# 06-Front_Panel_SFP_2.net
KiCad netlist of a schematic drawn in Altium Designer
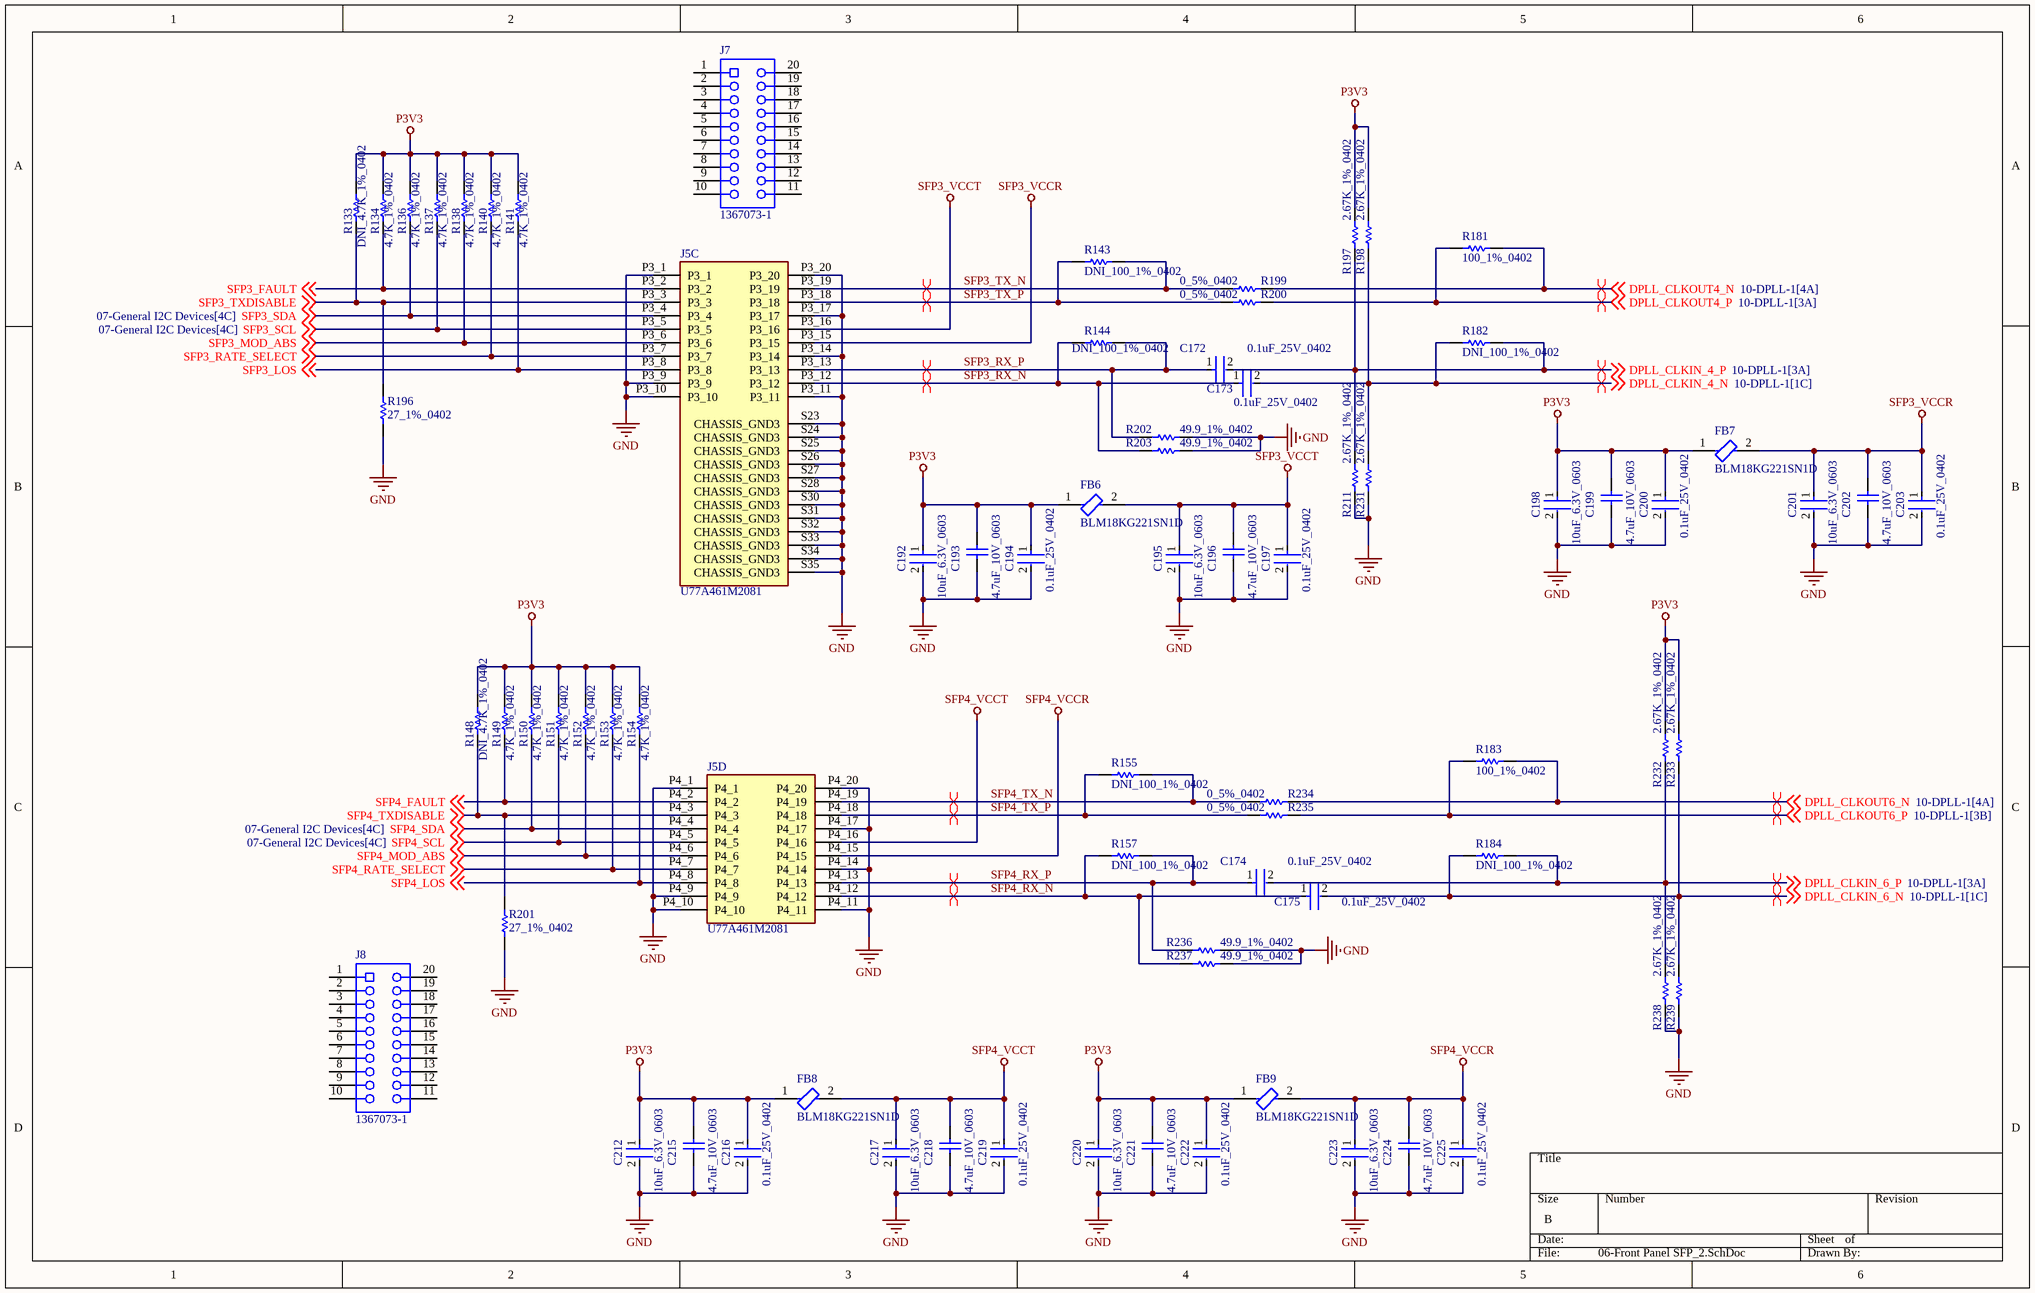
[diagram p0: 06-Front Panel SFP_2.SchDoc]

(export (version "E")
  (design (tool "Eeschema 10.0.6"))
  (components
    (comp (ref "C172")
      (value "0.1uF_25V_0402")
      (footprint "FP-0402-L_1_0_1-W_0_5_0_1-IPC_C")
      (description "General Purpose Ceramic Capacitor, 0402, 100nF, 10%, X7R, 15%, 25V")
      (fields (field (name "VOLTAGE") "25V") (field (name "TOLERANCE") "10%"))
      (libsource (lib "Altium Content Vault") (part "b4654b650e69147ec39a6b967a45e02"))
    )
    (comp (ref "C173")
      (value "0.1uF_25V_0402")
      (footprint "FP-0402-L_1_0_1-W_0_5_0_1-IPC_C")
      (description "General Purpose Ceramic Capacitor, 0402, 100nF, 10%, X7R, 15%, 25V")
      (fields (field (name "VOLTAGE") "25V") (field (name "TOLERANCE") "10%"))
      (libsource (lib "Altium Content Vault") (part "b4654b650e69147ec39a6b967a45e02"))
    )
    (comp (ref "C174")
      (value "0.1uF_25V_0402")
      (footprint "FP-0402-L_1_0_1-W_0_5_0_1-IPC_C")
      (description "General Purpose Ceramic Capacitor, 0402, 100nF, 10%, X7R, 15%, 25V")
      (fields (field (name "VOLTAGE") "25V") (field (name "TOLERANCE") "10%"))
      (libsource (lib "Altium Content Vault") (part "b4654b650e69147ec39a6b967a45e02"))
    )
    (comp (ref "C175")
      (value "0.1uF_25V_0402")
      (footprint "FP-0402-L_1_0_1-W_0_5_0_1-IPC_C")
      (description "General Purpose Ceramic Capacitor, 0402, 100nF, 10%, X7R, 15%, 25V")
      (fields (field (name "VOLTAGE") "25V") (field (name "TOLERANCE") "10%"))
      (libsource (lib "Altium Content Vault") (part "b4654b650e69147ec39a6b967a45e02"))
    )
    (comp (ref "C192")
      (value "10uF_6.3V_0603")
      (footprint "FP-C0603C106M9PACTU-MFG")
      (description "CAP CER 10UF 6.3V X5R 0603")
      (fields
        (field (name "MANUFACTURER PART NUMBER") "C0603C106M9PACTU")
        (field (name "MANUFACTURER") "Kemet")
      )
      (libsource (lib "Altium Content Vault") (part "b4654b650e69147ec39a6b967a45e02"))
    )
    (comp (ref "C193")
      (value "4.7uF_10V_0603")
      (footprint "CAPC1608X87X35NL15T15")
      (fields (field (name "PART NUMBER") "C0603C475K8PACTU") (field (name "MANUFACTURER") "Kemet"))
      (libsource (lib "Altium Content Vault") (part "CAP"))
    )
    (comp (ref "C194")
      (value "0.1uF_25V_0402")
      (footprint "FP-0402-L_1_0_1-W_0_5_0_1-IPC_C")
      (description "General Purpose Ceramic Capacitor, 0402, 100nF, 10%, X7R, 15%, 25V")
      (fields (field (name "VOLTAGE") "25V") (field (name "TOLERANCE") "10%"))
      (libsource (lib "Altium Content Vault") (part "b4654b650e69147ec39a6b967a45e02"))
    )
    (comp (ref "C195")
      (value "10uF_6.3V_0603")
      (footprint "FP-C0603C106M9PACTU-MFG")
      (description "CAP CER 10UF 6.3V X5R 0603")
      (fields
        (field (name "MANUFACTURER PART NUMBER") "C0603C106M9PACTU")
        (field (name "MANUFACTURER") "Kemet")
      )
      (libsource (lib "Altium Content Vault") (part "b4654b650e69147ec39a6b967a45e02"))
    )
    (comp (ref "C196")
      (value "4.7uF_10V_0603")
      (footprint "CAPC1608X87X35NL15T15")
      (fields (field (name "PART NUMBER") "C0603C475K8PACTU") (field (name "MANUFACTURER") "Kemet"))
      (libsource (lib "Altium Content Vault") (part "CAP"))
    )
    (comp (ref "C197")
      (value "0.1uF_25V_0402")
      (footprint "FP-0402-L_1_0_1-W_0_5_0_1-IPC_C")
      (description "General Purpose Ceramic Capacitor, 0402, 100nF, 10%, X7R, 15%, 25V")
      (fields (field (name "VOLTAGE") "25V") (field (name "TOLERANCE") "10%"))
      (libsource (lib "Altium Content Vault") (part "b4654b650e69147ec39a6b967a45e02"))
    )
    (comp (ref "C198")
      (value "10uF_6.3V_0603")
      (footprint "FP-C0603C106M9PACTU-MFG")
      (description "CAP CER 10UF 6.3V X5R 0603")
      (fields
        (field (name "MANUFACTURER PART NUMBER") "C0603C106M9PACTU")
        (field (name "MANUFACTURER") "Kemet")
      )
      (libsource (lib "Altium Content Vault") (part "b4654b650e69147ec39a6b967a45e02"))
    )
    (comp (ref "C199")
      (value "4.7uF_10V_0603")
      (footprint "CAPC1608X87X35NL15T15")
      (fields (field (name "PART NUMBER") "C0603C475K8PACTU") (field (name "MANUFACTURER") "Kemet"))
      (libsource (lib "Altium Content Vault") (part "CAP"))
    )
    (comp (ref "C200")
      (value "0.1uF_25V_0402")
      (footprint "FP-0402-L_1_0_1-W_0_5_0_1-IPC_C")
      (description "General Purpose Ceramic Capacitor, 0402, 100nF, 10%, X7R, 15%, 25V")
      (fields (field (name "VOLTAGE") "25V") (field (name "TOLERANCE") "10%"))
      (libsource (lib "Altium Content Vault") (part "b4654b650e69147ec39a6b967a45e02"))
    )
    (comp (ref "C201")
      (value "10uF_6.3V_0603")
      (footprint "FP-C0603C106M9PACTU-MFG")
      (description "CAP CER 10UF 6.3V X5R 0603")
      (fields
        (field (name "MANUFACTURER PART NUMBER") "C0603C106M9PACTU")
        (field (name "MANUFACTURER") "Kemet")
      )
      (libsource (lib "Altium Content Vault") (part "b4654b650e69147ec39a6b967a45e02"))
    )
    (comp (ref "C202")
      (value "4.7uF_10V_0603")
      (footprint "CAPC1608X87X35NL15T15")
      (fields (field (name "PART NUMBER") "C0603C475K8PACTU") (field (name "MANUFACTURER") "Kemet"))
      (libsource (lib "Altium Content Vault") (part "CAP"))
    )
    (comp (ref "C203")
      (value "0.1uF_25V_0402")
      (footprint "FP-0402-L_1_0_1-W_0_5_0_1-IPC_C")
      (description "General Purpose Ceramic Capacitor, 0402, 100nF, 10%, X7R, 15%, 25V")
      (fields (field (name "VOLTAGE") "25V") (field (name "TOLERANCE") "10%"))
      (libsource (lib "Altium Content Vault") (part "b4654b650e69147ec39a6b967a45e02"))
    )
    (comp (ref "C212")
      (value "10uF_6.3V_0603")
      (footprint "FP-C0603C106M9PACTU-MFG")
      (description "CAP CER 10UF 6.3V X5R 0603")
      (fields
        (field (name "MANUFACTURER PART NUMBER") "C0603C106M9PACTU")
        (field (name "MANUFACTURER") "Kemet")
      )
      (libsource (lib "Altium Content Vault") (part "b4654b650e69147ec39a6b967a45e02"))
    )
    (comp (ref "C215")
      (value "4.7uF_10V_0603")
      (footprint "CAPC1608X87X35NL15T15")
      (fields (field (name "PART NUMBER") "C0603C475K8PACTU") (field (name "MANUFACTURER") "Kemet"))
      (libsource (lib "Altium Content Vault") (part "CAP"))
    )
    (comp (ref "C216")
      (value "0.1uF_25V_0402")
      (footprint "FP-0402-L_1_0_1-W_0_5_0_1-IPC_C")
      (description "General Purpose Ceramic Capacitor, 0402, 100nF, 10%, X7R, 15%, 25V")
      (fields (field (name "VOLTAGE") "25V") (field (name "TOLERANCE") "10%"))
      (libsource (lib "Altium Content Vault") (part "b4654b650e69147ec39a6b967a45e02"))
    )
    (comp (ref "C217")
      (value "10uF_6.3V_0603")
      (footprint "FP-C0603C106M9PACTU-MFG")
      (description "CAP CER 10UF 6.3V X5R 0603")
      (fields
        (field (name "MANUFACTURER PART NUMBER") "C0603C106M9PACTU")
        (field (name "MANUFACTURER") "Kemet")
      )
      (libsource (lib "Altium Content Vault") (part "b4654b650e69147ec39a6b967a45e02"))
    )
    (comp (ref "C218")
      (value "4.7uF_10V_0603")
      (footprint "CAPC1608X87X35NL15T15")
      (fields (field (name "PART NUMBER") "C0603C475K8PACTU") (field (name "MANUFACTURER") "Kemet"))
      (libsource (lib "Altium Content Vault") (part "CAP"))
    )
    (comp (ref "C219")
      (value "0.1uF_25V_0402")
      (footprint "FP-0402-L_1_0_1-W_0_5_0_1-IPC_C")
      (description "General Purpose Ceramic Capacitor, 0402, 100nF, 10%, X7R, 15%, 25V")
      (fields (field (name "VOLTAGE") "25V") (field (name "TOLERANCE") "10%"))
      (libsource (lib "Altium Content Vault") (part "b4654b650e69147ec39a6b967a45e02"))
    )
    (comp (ref "C220")
      (value "10uF_6.3V_0603")
      (footprint "FP-C0603C106M9PACTU-MFG")
      (description "CAP CER 10UF 6.3V X5R 0603")
      (fields
        (field (name "MANUFACTURER PART NUMBER") "C0603C106M9PACTU")
        (field (name "MANUFACTURER") "Kemet")
      )
      (libsource (lib "Altium Content Vault") (part "b4654b650e69147ec39a6b967a45e02"))
    )
    (comp (ref "C221")
      (value "4.7uF_10V_0603")
      (footprint "CAPC1608X87X35NL15T15")
      (fields (field (name "PART NUMBER") "C0603C475K8PACTU") (field (name "MANUFACTURER") "Kemet"))
      (libsource (lib "Altium Content Vault") (part "CAP"))
    )
    (comp (ref "C222")
      (value "0.1uF_25V_0402")
      (footprint "FP-0402-L_1_0_1-W_0_5_0_1-IPC_C")
      (description "General Purpose Ceramic Capacitor, 0402, 100nF, 10%, X7R, 15%, 25V")
      (fields (field (name "VOLTAGE") "25V") (field (name "TOLERANCE") "10%"))
      (libsource (lib "Altium Content Vault") (part "b4654b650e69147ec39a6b967a45e02"))
    )
    (comp (ref "C223")
      (value "10uF_6.3V_0603")
      (footprint "FP-C0603C106M9PACTU-MFG")
      (description "CAP CER 10UF 6.3V X5R 0603")
      (fields
        (field (name "MANUFACTURER PART NUMBER") "C0603C106M9PACTU")
        (field (name "MANUFACTURER") "Kemet")
      )
      (libsource (lib "Altium Content Vault") (part "b4654b650e69147ec39a6b967a45e02"))
    )
    (comp (ref "C224")
      (value "4.7uF_10V_0603")
      (footprint "CAPC1608X87X35NL15T15")
      (fields (field (name "PART NUMBER") "C0603C475K8PACTU") (field (name "MANUFACTURER") "Kemet"))
      (libsource (lib "Altium Content Vault") (part "CAP"))
    )
    (comp (ref "C225")
      (value "0.1uF_25V_0402")
      (footprint "FP-0402-L_1_0_1-W_0_5_0_1-IPC_C")
      (description "General Purpose Ceramic Capacitor, 0402, 100nF, 10%, X7R, 15%, 25V")
      (fields (field (name "VOLTAGE") "25V") (field (name "TOLERANCE") "10%"))
      (libsource (lib "Altium Content Vault") (part "b4654b650e69147ec39a6b967a45e02"))
    )
    (comp (ref "FB6")
      (value "BLM18KG221SN1D")
      (footprint "FP-BLM18-0_15-t0_8-IPC_B")
      (description "Chip Ferrite Bead, 0603, 220Ω @ 100MHz, 0.05Ω, 25%, 2.2A")
      (fields (field (name "TOLERANCE") "25%"))
      (libsource (lib "Altium Content Vault") (part "5f30dd21d616792df468990f7003faa"))
    )
    (comp (ref "FB7")
      (value "BLM18KG221SN1D")
      (footprint "FP-BLM18-0_15-t0_8-IPC_B")
      (description "Chip Ferrite Bead, 0603, 220Ω @ 100MHz, 0.05Ω, 25%, 2.2A")
      (fields (field (name "TOLERANCE") "25%"))
      (libsource (lib "Altium Content Vault") (part "5f30dd21d616792df468990f7003faa"))
    )
    (comp (ref "FB8")
      (value "BLM18KG221SN1D")
      (footprint "FP-BLM18-0_15-t0_8-IPC_B")
      (description "Chip Ferrite Bead, 0603, 220Ω @ 100MHz, 0.05Ω, 25%, 2.2A")
      (fields (field (name "TOLERANCE") "25%"))
      (libsource (lib "Altium Content Vault") (part "5f30dd21d616792df468990f7003faa"))
    )
    (comp (ref "FB9")
      (value "BLM18KG221SN1D")
      (footprint "FP-BLM18-0_15-t0_8-IPC_B")
      (description "Chip Ferrite Bead, 0603, 220Ω @ 100MHz, 0.05Ω, 25%, 2.2A")
      (fields (field (name "TOLERANCE") "25%"))
      (libsource (lib "Altium Content Vault") (part "5f30dd21d616792df468990f7003faa"))
    )
    (comp (ref "J5")
      (value "U77A461M2081")
      (footprint "AMPHENOL_U77A461M2081")
      (fields (field (name "MF") "AMPHENOL ICC / FCI"))
      (libsource (lib "U77A461M2081") (part "U77A461M2081"))
    )
    (comp (ref "J7")
      (value "1367073-1")
      (footprint "TECO-1367073-1_V")
      (fields (field (name "MANUFACTURER") "TE Connectivity"))
      (libsource (lib "Altium Content Vault") (part "CN-2P-F-R20_B"))
    )
    (comp (ref "J8")
      (value "1367073-1")
      (footprint "TECO-1367073-1_V")
      (fields (field (name "MANUFACTURER") "TE Connectivity"))
      (libsource (lib "Altium Content Vault") (part "CN-2P-F-R20_B"))
    )
    (comp (ref "R133")
      (value "DNI_4.7K_1%_0402")
      (footprint "RESC1005X40X25NL10T10")
      (fields (field (name "MANUFACTURER") "Bourns") (field (name "PART NUMBER") "CR0402-FX-4701GLF"))
      (libsource (lib "Altium Content Vault") (part "RES"))
    )
    (comp (ref "R134")
      (value "4.7K_1%_0402")
      (footprint "RESC1005X40X25NL10T10")
      (fields (field (name "MANUFACTURER") "Bourns") (field (name "PART NUMBER") "CR0402-FX-4701GLF"))
      (libsource (lib "Altium Content Vault") (part "RES"))
    )
    (comp (ref "R136")
      (value "4.7K_1%_0402")
      (footprint "RESC1005X40X25NL10T10")
      (fields (field (name "MANUFACTURER") "Bourns") (field (name "PART NUMBER") "CR0402-FX-4701GLF"))
      (libsource (lib "Altium Content Vault") (part "RES"))
    )
    (comp (ref "R137")
      (value "4.7K_1%_0402")
      (footprint "RESC1005X40X25NL10T10")
      (fields (field (name "MANUFACTURER") "Bourns") (field (name "PART NUMBER") "CR0402-FX-4701GLF"))
      (libsource (lib "Altium Content Vault") (part "RES"))
    )
    (comp (ref "R138")
      (value "4.7K_1%_0402")
      (footprint "RESC1005X40X25NL10T10")
      (fields (field (name "MANUFACTURER") "Bourns") (field (name "PART NUMBER") "CR0402-FX-4701GLF"))
      (libsource (lib "Altium Content Vault") (part "RES"))
    )
    (comp (ref "R140")
      (value "4.7K_1%_0402")
      (footprint "RESC1005X40X25NL10T10")
      (fields (field (name "MANUFACTURER") "Bourns") (field (name "PART NUMBER") "CR0402-FX-4701GLF"))
      (libsource (lib "Altium Content Vault") (part "RES"))
    )
    (comp (ref "R141")
      (value "4.7K_1%_0402")
      (footprint "RESC1005X40X25NL10T10")
      (fields (field (name "MANUFACTURER") "Bourns") (field (name "PART NUMBER") "CR0402-FX-4701GLF"))
      (libsource (lib "Altium Content Vault") (part "RES"))
    )
    (comp (ref "R143")
      (value "DNI_100_1%_0402")
      (footprint "RESC1005X40X25NL05T10")
      (fields (field (name "MANUFACTURER") "Yageo") (field (name "PART NUMBER") "RC0402FR-13100RL"))
      (libsource (lib "Altium Content Vault") (part "RES"))
    )
    (comp (ref "R144")
      (value "DNI_100_1%_0402")
      (footprint "RESC1005X40X25NL05T10")
      (fields (field (name "MANUFACTURER") "Yageo") (field (name "PART NUMBER") "RC0402FR-13100RL"))
      (libsource (lib "Altium Content Vault") (part "RES"))
    )
    (comp (ref "R148")
      (value "DNI_4.7K_1%_0402")
      (footprint "RESC1005X40X25NL10T10")
      (fields (field (name "MANUFACTURER") "Bourns") (field (name "PART NUMBER") "CR0402-FX-4701GLF"))
      (libsource (lib "Altium Content Vault") (part "RES"))
    )
    (comp (ref "R149")
      (value "4.7K_1%_0402")
      (footprint "RESC1005X40X25NL10T10")
      (fields (field (name "MANUFACTURER") "Bourns") (field (name "PART NUMBER") "CR0402-FX-4701GLF"))
      (libsource (lib "Altium Content Vault") (part "RES"))
    )
    (comp (ref "R150")
      (value "4.7K_1%_0402")
      (footprint "RESC1005X40X25NL10T10")
      (fields (field (name "MANUFACTURER") "Bourns") (field (name "PART NUMBER") "CR0402-FX-4701GLF"))
      (libsource (lib "Altium Content Vault") (part "RES"))
    )
    (comp (ref "R151")
      (value "4.7K_1%_0402")
      (footprint "RESC1005X40X25NL10T10")
      (fields (field (name "MANUFACTURER") "Bourns") (field (name "PART NUMBER") "CR0402-FX-4701GLF"))
      (libsource (lib "Altium Content Vault") (part "RES"))
    )
    (comp (ref "R152")
      (value "4.7K_1%_0402")
      (footprint "RESC1005X40X25NL10T10")
      (fields (field (name "MANUFACTURER") "Bourns") (field (name "PART NUMBER") "CR0402-FX-4701GLF"))
      (libsource (lib "Altium Content Vault") (part "RES"))
    )
    (comp (ref "R153")
      (value "4.7K_1%_0402")
      (footprint "RESC1005X40X25NL10T10")
      (fields (field (name "MANUFACTURER") "Bourns") (field (name "PART NUMBER") "CR0402-FX-4701GLF"))
      (libsource (lib "Altium Content Vault") (part "RES"))
    )
    (comp (ref "R154")
      (value "4.7K_1%_0402")
      (footprint "RESC1005X40X25NL10T10")
      (fields (field (name "MANUFACTURER") "Bourns") (field (name "PART NUMBER") "CR0402-FX-4701GLF"))
      (libsource (lib "Altium Content Vault") (part "RES"))
    )
    (comp (ref "R155")
      (value "DNI_100_1%_0402")
      (footprint "RESC1005X40X25NL05T10")
      (fields (field (name "MANUFACTURER") "Yageo") (field (name "PART NUMBER") "RC0402FR-13100RL"))
      (libsource (lib "Altium Content Vault") (part "RES"))
    )
    (comp (ref "R157")
      (value "DNI_100_1%_0402")
      (footprint "RESC1005X40X25NL05T10")
      (fields (field (name "MANUFACTURER") "Yageo") (field (name "PART NUMBER") "RC0402FR-13100RL"))
      (libsource (lib "Altium Content Vault") (part "RES"))
    )
    (comp (ref "R181")
      (value "100_1%_0402")
      (footprint "RESC1005X40X25NL05T10")
      (fields (field (name "MANUFACTURER") "Yageo") (field (name "PART NUMBER") "RC0402FR-13100RL"))
      (libsource (lib "Altium Content Vault") (part "RES"))
    )
    (comp (ref "R182")
      (value "DNI_100_1%_0402")
      (footprint "RESC1005X40X25NL05T10")
      (fields (field (name "MANUFACTURER") "Yageo") (field (name "PART NUMBER") "RC0402FR-13100RL"))
      (libsource (lib "Altium Content Vault") (part "RES"))
    )
    (comp (ref "R183")
      (value "100_1%_0402")
      (footprint "RESC1005X40X25NL05T10")
      (fields (field (name "MANUFACTURER") "Yageo") (field (name "PART NUMBER") "RC0402FR-13100RL"))
      (libsource (lib "Altium Content Vault") (part "RES"))
    )
    (comp (ref "R184")
      (value "DNI_100_1%_0402")
      (footprint "RESC1005X40X25NL05T10")
      (fields (field (name "MANUFACTURER") "Yageo") (field (name "PART NUMBER") "RC0402FR-13100RL"))
      (libsource (lib "Altium Content Vault") (part "RES"))
    )
    (comp (ref "R196")
      (value "27_1%_0402")
      (footprint "RESC1005X40X25NL05T05")
      (fields (field (name "PART NUMBER") "CRCW040227R0FKED") (field (name "MANUFACTURER") "Vishay Dale"))
      (libsource (lib "Altium Content Vault") (part "RES"))
    )
    (comp (ref "R197")
      (value "2.67K_1%_0402")
      (footprint "RESC1005X40X25NL05T10")
      (fields (field (name "MANUFACTURER") "Yageo") (field (name "PART NUMBER") "RC0402FR-072K67L"))
      (libsource (lib "Altium Content Vault") (part "RES"))
    )
    (comp (ref "R198")
      (value "2.67K_1%_0402")
      (footprint "RESC1005X40X25NL05T10")
      (fields (field (name "MANUFACTURER") "Yageo") (field (name "PART NUMBER") "RC0402FR-072K67L"))
      (libsource (lib "Altium Content Vault") (part "RES"))
    )
    (comp (ref "R199")
      (value "0_5%_0402")
      (footprint "RESC1005X40X25LL10T10")
      (fields (field (name "MANUFACTURER") "KOA Speer") (field (name "PART NUMBER") "RK73Z1ETTP"))
      (libsource (lib "Altium Content Vault") (part "RES"))
    )
    (comp (ref "R200")
      (value "0_5%_0402")
      (footprint "RESC1005X40X25LL10T10")
      (fields (field (name "MANUFACTURER") "KOA Speer") (field (name "PART NUMBER") "RK73Z1ETTP"))
      (libsource (lib "Altium Content Vault") (part "RES"))
    )
    (comp (ref "R201")
      (value "27_1%_0402")
      (footprint "RESC1005X40X25NL05T05")
      (fields (field (name "PART NUMBER") "CRCW040227R0FKED") (field (name "MANUFACTURER") "Vishay Dale"))
      (libsource (lib "Altium Content Vault") (part "RES"))
    )
    (comp (ref "R202")
      (value "49.9_1%_0402")
      (footprint "RESC1005X40X25NL10T10")
      (fields (field (name "PART NUMBER") "RK73H1ETTP49R9F") (field (name "MANUFACTURER") "KOA Speer"))
      (libsource (lib "Altium Content Vault") (part "RES"))
    )
    (comp (ref "R203")
      (value "49.9_1%_0402")
      (footprint "RESC1005X40X25NL10T10")
      (fields (field (name "PART NUMBER") "RK73H1ETTP49R9F") (field (name "MANUFACTURER") "KOA Speer"))
      (libsource (lib "Altium Content Vault") (part "RES"))
    )
    (comp (ref "R211")
      (value "2.67K_1%_0402")
      (footprint "RESC1005X40X25NL05T10")
      (fields (field (name "MANUFACTURER") "Yageo") (field (name "PART NUMBER") "RC0402FR-072K67L"))
      (libsource (lib "Altium Content Vault") (part "RES"))
    )
    (comp (ref "R231")
      (value "2.67K_1%_0402")
      (footprint "RESC1005X40X25NL05T10")
      (fields (field (name "MANUFACTURER") "Yageo") (field (name "PART NUMBER") "RC0402FR-072K67L"))
      (libsource (lib "Altium Content Vault") (part "RES"))
    )
    (comp (ref "R232")
      (value "2.67K_1%_0402")
      (footprint "RESC1005X40X25NL05T10")
      (fields (field (name "MANUFACTURER") "Yageo") (field (name "PART NUMBER") "RC0402FR-072K67L"))
      (libsource (lib "Altium Content Vault") (part "RES"))
    )
    (comp (ref "R233")
      (value "2.67K_1%_0402")
      (footprint "RESC1005X40X25NL05T10")
      (fields (field (name "MANUFACTURER") "Yageo") (field (name "PART NUMBER") "RC0402FR-072K67L"))
      (libsource (lib "Altium Content Vault") (part "RES"))
    )
    (comp (ref "R234")
      (value "0_5%_0402")
      (footprint "RESC1005X40X25LL10T10")
      (fields (field (name "MANUFACTURER") "KOA Speer") (field (name "PART NUMBER") "RK73Z1ETTP"))
      (libsource (lib "Altium Content Vault") (part "RES"))
    )
    (comp (ref "R235")
      (value "0_5%_0402")
      (footprint "RESC1005X40X25LL10T10")
      (fields (field (name "MANUFACTURER") "KOA Speer") (field (name "PART NUMBER") "RK73Z1ETTP"))
      (libsource (lib "Altium Content Vault") (part "RES"))
    )
    (comp (ref "R236")
      (value "49.9_1%_0402")
      (footprint "RESC1005X40X25NL10T10")
      (fields (field (name "PART NUMBER") "RK73H1ETTP49R9F") (field (name "MANUFACTURER") "KOA Speer"))
      (libsource (lib "Altium Content Vault") (part "RES"))
    )
    (comp (ref "R237")
      (value "49.9_1%_0402")
      (footprint "RESC1005X40X25NL10T10")
      (fields (field (name "PART NUMBER") "RK73H1ETTP49R9F") (field (name "MANUFACTURER") "KOA Speer"))
      (libsource (lib "Altium Content Vault") (part "RES"))
    )
    (comp (ref "R238")
      (value "2.67K_1%_0402")
      (footprint "RESC1005X40X25NL05T10")
      (fields (field (name "MANUFACTURER") "Yageo") (field (name "PART NUMBER") "RC0402FR-072K67L"))
      (libsource (lib "Altium Content Vault") (part "RES"))
    )
    (comp (ref "R239")
      (value "2.67K_1%_0402")
      (footprint "RESC1005X40X25NL05T10")
      (fields (field (name "MANUFACTURER") "Yageo") (field (name "PART NUMBER") "RC0402FR-072K67L"))
      (libsource (lib "Altium Content Vault") (part "RES"))
    )
  )
  (nets
    (net (code "1") (name "/SFP3_RX_N") (class "Default")
      (node (ref "C173") (pin "1") (pinfunction "1_1") (pintype "passive"))
      (node (ref "J5") (pin "P3_12") (pinfunction "P3_12_P3_12") (pintype "passive"))
      (node (ref "R144") (pin "1") (pinfunction "1_1") (pintype "passive"))
      (node (ref "R203") (pin "1") (pinfunction "1_1") (pintype "passive"))
    )
    (net (code "2") (name "/SFP3_RX_P") (class "Default")
      (node (ref "C172") (pin "1") (pinfunction "1_1") (pintype "passive"))
      (node (ref "J5") (pin "P3_13") (pinfunction "P3_13_P3_13") (pintype "passive"))
      (node (ref "R144") (pin "2") (pinfunction "2_2") (pintype "passive"))
      (node (ref "R202") (pin "1") (pinfunction "1_1") (pintype "passive"))
    )
    (net (code "3") (name "/SFP3_TX_N") (class "Default")
      (node (ref "J5") (pin "P3_19") (pinfunction "P3_19_P3_19") (pintype "passive"))
      (node (ref "R143") (pin "2") (pinfunction "2_2") (pintype "passive"))
      (node (ref "R199") (pin "1") (pinfunction "1_1") (pintype "passive"))
    )
    (net (code "4") (name "/SFP3_TX_P") (class "Default")
      (node (ref "J5") (pin "P3_18") (pinfunction "P3_18_P3_18") (pintype "passive"))
      (node (ref "R143") (pin "1") (pinfunction "1_1") (pintype "passive"))
      (node (ref "R200") (pin "1") (pinfunction "1_1") (pintype "passive"))
    )
    (net (code "5") (name "/SFP4_RX_N") (class "Default")
      (node (ref "C175") (pin "1") (pinfunction "1_1") (pintype "passive"))
      (node (ref "J5") (pin "P4_12") (pinfunction "P4_12_P4_12") (pintype "passive"))
      (node (ref "R157") (pin "1") (pinfunction "1_1") (pintype "passive"))
      (node (ref "R237") (pin "1") (pinfunction "1_1") (pintype "passive"))
    )
    (net (code "6") (name "/SFP4_RX_P") (class "Default")
      (node (ref "C174") (pin "1") (pinfunction "1_1") (pintype "passive"))
      (node (ref "J5") (pin "P4_13") (pinfunction "P4_13_P4_13") (pintype "passive"))
      (node (ref "R157") (pin "2") (pinfunction "2_2") (pintype "passive"))
      (node (ref "R236") (pin "1") (pinfunction "1_1") (pintype "passive"))
    )
    (net (code "7") (name "/SFP4_TX_N") (class "Default")
      (node (ref "J5") (pin "P4_19") (pinfunction "P4_19_P4_19") (pintype "passive"))
      (node (ref "R155") (pin "2") (pinfunction "2_2") (pintype "passive"))
      (node (ref "R234") (pin "1") (pinfunction "1_1") (pintype "passive"))
    )
    (net (code "8") (name "/SFP4_TX_P") (class "Default")
      (node (ref "J5") (pin "P4_18") (pinfunction "P4_18_P4_18") (pintype "passive"))
      (node (ref "R155") (pin "1") (pinfunction "1_1") (pintype "passive"))
      (node (ref "R235") (pin "1") (pinfunction "1_1") (pintype "passive"))
    )
    (net (code "9") (name "DPLL_CLKIN_4_N") (class "Default")
      (node (ref "C173") (pin "2") (pinfunction "2_2") (pintype "passive"))
      (node (ref "R182") (pin "1") (pinfunction "1_1") (pintype "passive"))
      (node (ref "R198") (pin "1") (pinfunction "1_1") (pintype "passive"))
      (node (ref "R231") (pin "2") (pinfunction "2_2") (pintype "passive"))
    )
    (net (code "10") (name "DPLL_CLKIN_4_P") (class "Default")
      (node (ref "C172") (pin "2") (pinfunction "2_2") (pintype "passive"))
      (node (ref "R182") (pin "2") (pinfunction "2_2") (pintype "passive"))
      (node (ref "R197") (pin "1") (pinfunction "1_1") (pintype "passive"))
      (node (ref "R211") (pin "2") (pinfunction "2_2") (pintype "passive"))
    )
    (net (code "11") (name "DPLL_CLKIN_6_N") (class "Default")
      (node (ref "C175") (pin "2") (pinfunction "2_2") (pintype "passive"))
      (node (ref "R184") (pin "1") (pinfunction "1_1") (pintype "passive"))
      (node (ref "R233") (pin "1") (pinfunction "1_1") (pintype "passive"))
      (node (ref "R239") (pin "2") (pinfunction "2_2") (pintype "passive"))
    )
    (net (code "12") (name "DPLL_CLKIN_6_P") (class "Default")
      (node (ref "C174") (pin "2") (pinfunction "2_2") (pintype "passive"))
      (node (ref "R184") (pin "2") (pinfunction "2_2") (pintype "passive"))
      (node (ref "R232") (pin "1") (pinfunction "1_1") (pintype "passive"))
      (node (ref "R238") (pin "2") (pinfunction "2_2") (pintype "passive"))
    )
    (net (code "13") (name "DPLL_CLKOUT4_N") (class "Default")
      (node (ref "R181") (pin "2") (pinfunction "2_2") (pintype "passive"))
      (node (ref "R199") (pin "2") (pinfunction "2_2") (pintype "passive"))
    )
    (net (code "14") (name "DPLL_CLKOUT4_P") (class "Default")
      (node (ref "R181") (pin "1") (pinfunction "1_1") (pintype "passive"))
      (node (ref "R200") (pin "2") (pinfunction "2_2") (pintype "passive"))
    )
    (net (code "15") (name "DPLL_CLKOUT6_N") (class "Default")
      (node (ref "R183") (pin "2") (pinfunction "2_2") (pintype "passive"))
      (node (ref "R234") (pin "2") (pinfunction "2_2") (pintype "passive"))
    )
    (net (code "16") (name "DPLL_CLKOUT6_P") (class "Default")
      (node (ref "R183") (pin "1") (pinfunction "1_1") (pintype "passive"))
      (node (ref "R235") (pin "2") (pinfunction "2_2") (pintype "passive"))
    )
    (net (code "17") (name "GND") (class "Default")
      (node (ref "C192") (pin "2") (pinfunction "2_2") (pintype "passive"))
      (node (ref "C193") (pin "1") (pinfunction "1_1") (pintype "passive"))
      (node (ref "C194") (pin "2") (pinfunction "2_2") (pintype "passive"))
      (node (ref "C195") (pin "2") (pinfunction "2_2") (pintype "passive"))
      (node (ref "C196") (pin "1") (pinfunction "1_1") (pintype "passive"))
      (node (ref "C197") (pin "2") (pinfunction "2_2") (pintype "passive"))
      (node (ref "C198") (pin "2") (pinfunction "2_2") (pintype "passive"))
      (node (ref "C199") (pin "1") (pinfunction "1_1") (pintype "passive"))
      (node (ref "C200") (pin "2") (pinfunction "2_2") (pintype "passive"))
      (node (ref "C201") (pin "2") (pinfunction "2_2") (pintype "passive"))
      (node (ref "C202") (pin "1") (pinfunction "1_1") (pintype "passive"))
      (node (ref "C203") (pin "2") (pinfunction "2_2") (pintype "passive"))
      (node (ref "C212") (pin "2") (pinfunction "2_2") (pintype "passive"))
      (node (ref "C215") (pin "1") (pinfunction "1_1") (pintype "passive"))
      (node (ref "C216") (pin "2") (pinfunction "2_2") (pintype "passive"))
      (node (ref "C217") (pin "2") (pinfunction "2_2") (pintype "passive"))
      (node (ref "C218") (pin "1") (pinfunction "1_1") (pintype "passive"))
      (node (ref "C219") (pin "2") (pinfunction "2_2") (pintype "passive"))
      (node (ref "C220") (pin "2") (pinfunction "2_2") (pintype "passive"))
      (node (ref "C221") (pin "1") (pinfunction "1_1") (pintype "passive"))
      (node (ref "C222") (pin "2") (pinfunction "2_2") (pintype "passive"))
      (node (ref "C223") (pin "2") (pinfunction "2_2") (pintype "passive"))
      (node (ref "C224") (pin "1") (pinfunction "1_1") (pintype "passive"))
      (node (ref "C225") (pin "2") (pinfunction "2_2") (pintype "passive"))
      (node (ref "J5") (pin "P3_1") (pinfunction "P3_1_P3_1") (pintype "passive"))
      (node (ref "J5") (pin "P3_10") (pinfunction "P3_10_P3_10") (pintype "passive"))
      (node (ref "J5") (pin "P3_11") (pinfunction "P3_11_P3_11") (pintype "passive"))
      (node (ref "J5") (pin "P3_14") (pinfunction "P3_14_P3_14") (pintype "passive"))
      (node (ref "J5") (pin "P3_17") (pinfunction "P3_17_P3_17") (pintype "passive"))
      (node (ref "J5") (pin "P3_20") (pinfunction "P3_20_P3_20") (pintype "passive"))
      (node (ref "J5") (pin "P3_9") (pinfunction "P3_9_P3_9") (pintype "passive"))
      (node (ref "J5") (pin "P4_1") (pinfunction "P4_1_P4_1") (pintype "passive"))
      (node (ref "J5") (pin "P4_10") (pinfunction "P4_10_P4_10") (pintype "passive"))
      (node (ref "J5") (pin "P4_11") (pinfunction "P4_11_P4_11") (pintype "passive"))
      (node (ref "J5") (pin "P4_14") (pinfunction "P4_14_P4_14") (pintype "passive"))
      (node (ref "J5") (pin "P4_17") (pinfunction "P4_17_P4_17") (pintype "passive"))
      (node (ref "J5") (pin "P4_20") (pinfunction "P4_20_P4_20") (pintype "passive"))
      (node (ref "J5") (pin "P4_9") (pinfunction "P4_9_P4_9") (pintype "passive"))
      (node (ref "J5") (pin "S23") (pinfunction "CHASSIS_GND3_S23") (pintype "passive"))
      (node (ref "J5") (pin "S24") (pinfunction "CHASSIS_GND3_S24") (pintype "passive"))
      (node (ref "J5") (pin "S25") (pinfunction "CHASSIS_GND3_S25") (pintype "passive"))
      (node (ref "J5") (pin "S26") (pinfunction "CHASSIS_GND3_S26") (pintype "passive"))
      (node (ref "J5") (pin "S27") (pinfunction "CHASSIS_GND3_S27") (pintype "passive"))
      (node (ref "J5") (pin "S28") (pinfunction "CHASSIS_GND3_S28") (pintype "passive"))
      (node (ref "J5") (pin "S30") (pinfunction "CHASSIS_GND3_S30") (pintype "passive"))
      (node (ref "J5") (pin "S31") (pinfunction "CHASSIS_GND3_S31") (pintype "passive"))
      (node (ref "J5") (pin "S32") (pinfunction "CHASSIS_GND3_S32") (pintype "passive"))
      (node (ref "J5") (pin "S33") (pinfunction "CHASSIS_GND3_S33") (pintype "passive"))
      (node (ref "J5") (pin "S34") (pinfunction "CHASSIS_GND3_S34") (pintype "passive"))
      (node (ref "J5") (pin "S35") (pinfunction "CHASSIS_GND3_S35") (pintype "passive"))
      (node (ref "R196") (pin "1") (pinfunction "1_1") (pintype "passive"))
      (node (ref "R201") (pin "1") (pinfunction "1_1") (pintype "passive"))
      (node (ref "R202") (pin "2") (pinfunction "2_2") (pintype "passive"))
      (node (ref "R203") (pin "2") (pinfunction "2_2") (pintype "passive"))
      (node (ref "R211") (pin "1") (pinfunction "1_1") (pintype "passive"))
      (node (ref "R231") (pin "1") (pinfunction "1_1") (pintype "passive"))
      (node (ref "R236") (pin "2") (pinfunction "2_2") (pintype "passive"))
      (node (ref "R237") (pin "2") (pinfunction "2_2") (pintype "passive"))
      (node (ref "R238") (pin "1") (pinfunction "1_1") (pintype "passive"))
      (node (ref "R239") (pin "1") (pinfunction "1_1") (pintype "passive"))
    )
    (net (code "18") (name "P3V3") (class "Default")
      (node (ref "C192") (pin "1") (pinfunction "1_1") (pintype "passive"))
      (node (ref "C193") (pin "2") (pinfunction "2_2") (pintype "passive"))
      (node (ref "C194") (pin "1") (pinfunction "1_1") (pintype "passive"))
      (node (ref "C198") (pin "1") (pinfunction "1_1") (pintype "passive"))
      (node (ref "C199") (pin "2") (pinfunction "2_2") (pintype "passive"))
      (node (ref "C200") (pin "1") (pinfunction "1_1") (pintype "passive"))
      (node (ref "C212") (pin "1") (pinfunction "1_1") (pintype "passive"))
      (node (ref "C215") (pin "2") (pinfunction "2_2") (pintype "passive"))
      (node (ref "C216") (pin "1") (pinfunction "1_1") (pintype "passive"))
      (node (ref "C220") (pin "1") (pinfunction "1_1") (pintype "passive"))
      (node (ref "C221") (pin "2") (pinfunction "2_2") (pintype "passive"))
      (node (ref "C222") (pin "1") (pinfunction "1_1") (pintype "passive"))
      (node (ref "FB6") (pin "1") (pinfunction "1_1") (pintype "passive"))
      (node (ref "FB7") (pin "1") (pinfunction "1_1") (pintype "passive"))
      (node (ref "FB8") (pin "1") (pinfunction "1_1") (pintype "passive"))
      (node (ref "FB9") (pin "1") (pinfunction "1_1") (pintype "passive"))
      (node (ref "R133") (pin "1") (pinfunction "1_1") (pintype "passive"))
      (node (ref "R134") (pin "1") (pinfunction "1_1") (pintype "passive"))
      (node (ref "R136") (pin "1") (pinfunction "1_1") (pintype "passive"))
      (node (ref "R137") (pin "1") (pinfunction "1_1") (pintype "passive"))
      (node (ref "R138") (pin "1") (pinfunction "1_1") (pintype "passive"))
      (node (ref "R140") (pin "1") (pinfunction "1_1") (pintype "passive"))
      (node (ref "R141") (pin "1") (pinfunction "1_1") (pintype "passive"))
      (node (ref "R148") (pin "1") (pinfunction "1_1") (pintype "passive"))
      (node (ref "R149") (pin "1") (pinfunction "1_1") (pintype "passive"))
      (node (ref "R150") (pin "1") (pinfunction "1_1") (pintype "passive"))
      (node (ref "R151") (pin "1") (pinfunction "1_1") (pintype "passive"))
      (node (ref "R152") (pin "1") (pinfunction "1_1") (pintype "passive"))
      (node (ref "R153") (pin "1") (pinfunction "1_1") (pintype "passive"))
      (node (ref "R154") (pin "1") (pinfunction "1_1") (pintype "passive"))
      (node (ref "R197") (pin "2") (pinfunction "2_2") (pintype "passive"))
      (node (ref "R198") (pin "2") (pinfunction "2_2") (pintype "passive"))
      (node (ref "R232") (pin "2") (pinfunction "2_2") (pintype "passive"))
      (node (ref "R233") (pin "2") (pinfunction "2_2") (pintype "passive"))
    )
    (net (code "19") (name "SFP3_FAULT") (class "Default")
      (node (ref "J5") (pin "P3_2") (pinfunction "P3_2_P3_2") (pintype "passive"))
      (node (ref "R134") (pin "2") (pinfunction "2_2") (pintype "passive"))
    )
    (net (code "20") (name "SFP3_LOS") (class "Default")
      (node (ref "J5") (pin "P3_8") (pinfunction "P3_8_P3_8") (pintype "passive"))
      (node (ref "R141") (pin "2") (pinfunction "2_2") (pintype "passive"))
    )
    (net (code "21") (name "SFP3_MOD_ABS") (class "Default")
      (node (ref "J5") (pin "P3_6") (pinfunction "P3_6_P3_6") (pintype "passive"))
      (node (ref "R138") (pin "2") (pinfunction "2_2") (pintype "passive"))
    )
    (net (code "22") (name "SFP3_RATE_SELECT") (class "Default")
      (node (ref "J5") (pin "P3_7") (pinfunction "P3_7_P3_7") (pintype "passive"))
      (node (ref "R140") (pin "2") (pinfunction "2_2") (pintype "passive"))
    )
    (net (code "23") (name "SFP3_SCL") (class "Default")
      (node (ref "J5") (pin "P3_5") (pinfunction "P3_5_P3_5") (pintype "passive"))
      (node (ref "R137") (pin "2") (pinfunction "2_2") (pintype "passive"))
    )
    (net (code "24") (name "SFP3_SDA") (class "Default")
      (node (ref "J5") (pin "P3_4") (pinfunction "P3_4_P3_4") (pintype "passive"))
      (node (ref "R136") (pin "2") (pinfunction "2_2") (pintype "passive"))
    )
    (net (code "25") (name "SFP3_TXDISABLE") (class "Default")
      (node (ref "J5") (pin "P3_3") (pinfunction "P3_3_P3_3") (pintype "passive"))
      (node (ref "R133") (pin "2") (pinfunction "2_2") (pintype "passive"))
      (node (ref "R196") (pin "2") (pinfunction "2_2") (pintype "passive"))
    )
    (net (code "26") (name "SFP3_VCCR") (class "Default")
      (node (ref "C201") (pin "1") (pinfunction "1_1") (pintype "passive"))
      (node (ref "C202") (pin "2") (pinfunction "2_2") (pintype "passive"))
      (node (ref "C203") (pin "1") (pinfunction "1_1") (pintype "passive"))
      (node (ref "FB7") (pin "2") (pinfunction "2_2") (pintype "passive"))
      (node (ref "J5") (pin "P3_15") (pinfunction "P3_15_P3_15") (pintype "passive"))
    )
    (net (code "27") (name "SFP3_VCCT") (class "Default")
      (node (ref "C195") (pin "1") (pinfunction "1_1") (pintype "passive"))
      (node (ref "C196") (pin "2") (pinfunction "2_2") (pintype "passive"))
      (node (ref "C197") (pin "1") (pinfunction "1_1") (pintype "passive"))
      (node (ref "FB6") (pin "2") (pinfunction "2_2") (pintype "passive"))
      (node (ref "J5") (pin "P3_16") (pinfunction "P3_16_P3_16") (pintype "passive"))
    )
    (net (code "28") (name "SFP4_FAULT") (class "Default")
      (node (ref "J5") (pin "P4_2") (pinfunction "P4_2_P4_2") (pintype "passive"))
      (node (ref "R149") (pin "2") (pinfunction "2_2") (pintype "passive"))
    )
    (net (code "29") (name "SFP4_LOS") (class "Default")
      (node (ref "J5") (pin "P4_8") (pinfunction "P4_8_P4_8") (pintype "passive"))
      (node (ref "R154") (pin "2") (pinfunction "2_2") (pintype "passive"))
    )
    (net (code "30") (name "SFP4_MOD_ABS") (class "Default")
      (node (ref "J5") (pin "P4_6") (pinfunction "P4_6_P4_6") (pintype "passive"))
      (node (ref "R152") (pin "2") (pinfunction "2_2") (pintype "passive"))
    )
    (net (code "31") (name "SFP4_RATE_SELECT") (class "Default")
      (node (ref "J5") (pin "P4_7") (pinfunction "P4_7_P4_7") (pintype "passive"))
      (node (ref "R153") (pin "2") (pinfunction "2_2") (pintype "passive"))
    )
    (net (code "32") (name "SFP4_SCL") (class "Default")
      (node (ref "J5") (pin "P4_5") (pinfunction "P4_5_P4_5") (pintype "passive"))
      (node (ref "R151") (pin "2") (pinfunction "2_2") (pintype "passive"))
    )
    (net (code "33") (name "SFP4_SDA") (class "Default")
      (node (ref "J5") (pin "P4_4") (pinfunction "P4_4_P4_4") (pintype "passive"))
      (node (ref "R150") (pin "2") (pinfunction "2_2") (pintype "passive"))
    )
    (net (code "34") (name "SFP4_TXDISABLE") (class "Default")
      (node (ref "J5") (pin "P4_3") (pinfunction "P4_3_P4_3") (pintype "passive"))
      (node (ref "R148") (pin "2") (pinfunction "2_2") (pintype "passive"))
      (node (ref "R201") (pin "2") (pinfunction "2_2") (pintype "passive"))
    )
    (net (code "35") (name "SFP4_VCCR") (class "Default")
      (node (ref "C223") (pin "1") (pinfunction "1_1") (pintype "passive"))
      (node (ref "C224") (pin "2") (pinfunction "2_2") (pintype "passive"))
      (node (ref "C225") (pin "1") (pinfunction "1_1") (pintype "passive"))
      (node (ref "FB9") (pin "2") (pinfunction "2_2") (pintype "passive"))
      (node (ref "J5") (pin "P4_15") (pinfunction "P4_15_P4_15") (pintype "passive"))
    )
    (net (code "36") (name "SFP4_VCCT") (class "Default")
      (node (ref "C217") (pin "1") (pinfunction "1_1") (pintype "passive"))
      (node (ref "C218") (pin "2") (pinfunction "2_2") (pintype "passive"))
      (node (ref "C219") (pin "1") (pinfunction "1_1") (pintype "passive"))
      (node (ref "FB8") (pin "2") (pinfunction "2_2") (pintype "passive"))
      (node (ref "J5") (pin "P4_16") (pinfunction "P4_16_P4_16") (pintype "passive"))
    )
    (net (code "37") (name "unconnected-(J7-Pad1)") (class "Default")
      (node (ref "J7") (pin "1") (pinfunction "1_1") (pintype "passive"))
    )
    (net (code "38") (name "unconnected-(J7-Pad2)") (class "Default")
      (node (ref "J7") (pin "2") (pinfunction "2_2") (pintype "passive"))
    )
    (net (code "39") (name "unconnected-(J7-Pad3)") (class "Default")
      (node (ref "J7") (pin "3") (pinfunction "3_3") (pintype "passive"))
    )
    (net (code "40") (name "unconnected-(J7-Pad4)") (class "Default")
      (node (ref "J7") (pin "4") (pinfunction "4_4") (pintype "passive"))
    )
    (net (code "41") (name "unconnected-(J7-Pad5)") (class "Default")
      (node (ref "J7") (pin "5") (pinfunction "5_5") (pintype "passive"))
    )
    (net (code "42") (name "unconnected-(J7-Pad6)") (class "Default")
      (node (ref "J7") (pin "6") (pinfunction "6_6") (pintype "passive"))
    )
    (net (code "43") (name "unconnected-(J7-Pad7)") (class "Default")
      (node (ref "J7") (pin "7") (pinfunction "7_7") (pintype "passive"))
    )
    (net (code "44") (name "unconnected-(J7-Pad8)") (class "Default")
      (node (ref "J7") (pin "8") (pinfunction "8_8") (pintype "passive"))
    )
    (net (code "45") (name "unconnected-(J7-Pad9)") (class "Default")
      (node (ref "J7") (pin "9") (pinfunction "9_9") (pintype "passive"))
    )
    (net (code "46") (name "unconnected-(J7-Pad10)") (class "Default")
      (node (ref "J7") (pin "10") (pinfunction "10_10") (pintype "passive"))
    )
    (net (code "47") (name "unconnected-(J7-Pad11)") (class "Default")
      (node (ref "J7") (pin "11") (pinfunction "11_11") (pintype "passive"))
    )
    (net (code "48") (name "unconnected-(J7-Pad12)") (class "Default")
      (node (ref "J7") (pin "12") (pinfunction "12_12") (pintype "passive"))
    )
    (net (code "49") (name "unconnected-(J7-Pad13)") (class "Default")
      (node (ref "J7") (pin "13") (pinfunction "13_13") (pintype "passive"))
    )
    (net (code "50") (name "unconnected-(J7-Pad14)") (class "Default")
      (node (ref "J7") (pin "14") (pinfunction "14_14") (pintype "passive"))
    )
    (net (code "51") (name "unconnected-(J7-Pad15)") (class "Default")
      (node (ref "J7") (pin "15") (pinfunction "15_15") (pintype "passive"))
    )
    (net (code "52") (name "unconnected-(J7-Pad16)") (class "Default")
      (node (ref "J7") (pin "16") (pinfunction "16_16") (pintype "passive"))
    )
    (net (code "53") (name "unconnected-(J7-Pad17)") (class "Default")
      (node (ref "J7") (pin "17") (pinfunction "17_17") (pintype "passive"))
    )
    (net (code "54") (name "unconnected-(J7-Pad18)") (class "Default")
      (node (ref "J7") (pin "18") (pinfunction "18_18") (pintype "passive"))
    )
    (net (code "55") (name "unconnected-(J7-Pad19)") (class "Default")
      (node (ref "J7") (pin "19") (pinfunction "19_19") (pintype "passive"))
    )
    (net (code "56") (name "unconnected-(J7-Pad20)") (class "Default")
      (node (ref "J7") (pin "20") (pinfunction "20_20") (pintype "passive"))
    )
    (net (code "57") (name "unconnected-(J8-Pad1)") (class "Default")
      (node (ref "J8") (pin "1") (pinfunction "1_1") (pintype "passive"))
    )
    (net (code "58") (name "unconnected-(J8-Pad2)") (class "Default")
      (node (ref "J8") (pin "2") (pinfunction "2_2") (pintype "passive"))
    )
    (net (code "59") (name "unconnected-(J8-Pad3)") (class "Default")
      (node (ref "J8") (pin "3") (pinfunction "3_3") (pintype "passive"))
    )
    (net (code "60") (name "unconnected-(J8-Pad4)") (class "Default")
      (node (ref "J8") (pin "4") (pinfunction "4_4") (pintype "passive"))
    )
    (net (code "61") (name "unconnected-(J8-Pad5)") (class "Default")
      (node (ref "J8") (pin "5") (pinfunction "5_5") (pintype "passive"))
    )
    (net (code "62") (name "unconnected-(J8-Pad6)") (class "Default")
      (node (ref "J8") (pin "6") (pinfunction "6_6") (pintype "passive"))
    )
    (net (code "63") (name "unconnected-(J8-Pad7)") (class "Default")
      (node (ref "J8") (pin "7") (pinfunction "7_7") (pintype "passive"))
    )
    (net (code "64") (name "unconnected-(J8-Pad8)") (class "Default")
      (node (ref "J8") (pin "8") (pinfunction "8_8") (pintype "passive"))
    )
    (net (code "65") (name "unconnected-(J8-Pad9)") (class "Default")
      (node (ref "J8") (pin "9") (pinfunction "9_9") (pintype "passive"))
    )
    (net (code "66") (name "unconnected-(J8-Pad10)") (class "Default")
      (node (ref "J8") (pin "10") (pinfunction "10_10") (pintype "passive"))
    )
    (net (code "67") (name "unconnected-(J8-Pad11)") (class "Default")
      (node (ref "J8") (pin "11") (pinfunction "11_11") (pintype "passive"))
    )
    (net (code "68") (name "unconnected-(J8-Pad12)") (class "Default")
      (node (ref "J8") (pin "12") (pinfunction "12_12") (pintype "passive"))
    )
    (net (code "69") (name "unconnected-(J8-Pad13)") (class "Default")
      (node (ref "J8") (pin "13") (pinfunction "13_13") (pintype "passive"))
    )
    (net (code "70") (name "unconnected-(J8-Pad14)") (class "Default")
      (node (ref "J8") (pin "14") (pinfunction "14_14") (pintype "passive"))
    )
    (net (code "71") (name "unconnected-(J8-Pad15)") (class "Default")
      (node (ref "J8") (pin "15") (pinfunction "15_15") (pintype "passive"))
    )
    (net (code "72") (name "unconnected-(J8-Pad16)") (class "Default")
      (node (ref "J8") (pin "16") (pinfunction "16_16") (pintype "passive"))
    )
    (net (code "73") (name "unconnected-(J8-Pad17)") (class "Default")
      (node (ref "J8") (pin "17") (pinfunction "17_17") (pintype "passive"))
    )
    (net (code "74") (name "unconnected-(J8-Pad18)") (class "Default")
      (node (ref "J8") (pin "18") (pinfunction "18_18") (pintype "passive"))
    )
    (net (code "75") (name "unconnected-(J8-Pad19)") (class "Default")
      (node (ref "J8") (pin "19") (pinfunction "19_19") (pintype "passive"))
    )
    (net (code "76") (name "unconnected-(J8-Pad20)") (class "Default")
      (node (ref "J8") (pin "20") (pinfunction "20_20") (pintype "passive"))
    )
  )
)
